# microSD.net
KiCad netlist of a schematic drawn in Altium Designer
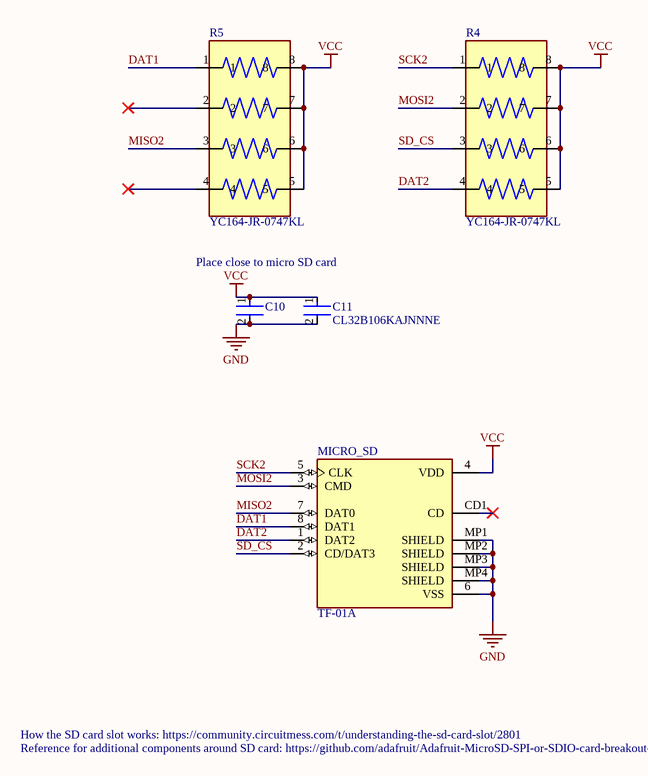
[diagram p0: microSD.SchDoc]

(export (version "E")
  (design (tool "Eeschema 10.0.6"))
  (components
    (comp (ref "C10")
      (value "CC0603KRX7R9BB104")
      (footprint "FP-CC0603-DA-MFG")
      (description "CAP CER 0.1UF 50V X7R 0603")
      (fields (field (name "MANUFACTURER") "YAGEO") (field (name "VOLTAGE") "50 V"))
      (libsource (lib "Altium Content Vault") (part "11868f565c42a9108669ba33697ecf6"))
    )
    (comp (ref "C11")
      (value "CL32B106KAJNNNE")
      (footprint "FP-CL32-IPC_B")
      (description "Cap Ceramic 10uF 25V X7R ±10% SMD 1210 +125°C Embossed T/R")
      (fields (field (name "TOLERANCE") "10%") (field (name "VOLTAGE") "25V"))
      (libsource (lib "Altium Content Vault") (part "b4654b650e69147ec39a6b967a45e02"))
    )
    (comp (ref "MICRO_SD")
      (value "TF-01A")
      (footprint "TF-01A")
      (description "Standard Card Edge Connectors")
      (fields (field (name "MF") "HRO Electronics Co., Ltd.") (field (name "LCSC PART #") "C91145"))
      (libsource (lib "TF-01A") (part "TF-01A"))
    )
    (comp (ref "R4")
      (value "YC164-JR-0747KL")
      (footprint "RESCAXE80P320X160X70-8N")
      (fields (field (name "MF") "Yageo") (field (name "LCSC PART #") "C779384"))
      (libsource (lib "YC164-JR-0747KL") (part "YC164-JR-0747KL"))
    )
    (comp (ref "R5")
      (value "YC164-JR-0747KL")
      (footprint "RESCAXE80P320X160X70-8N")
      (fields (field (name "MF") "Yageo") (field (name "LCSC PART #") "C779384"))
      (libsource (lib "YC164-JR-0747KL") (part "YC164-JR-0747KL"))
    )
  )
  (nets
    (net (code "1") (name "/DAT1") (class "Default")
      (node (ref "MICRO_SD") (pin "8") (pinfunction "DAT1_8") (pintype "bidirectional"))
      (node (ref "R5") (pin "1") (pinfunction "1_1") (pintype "passive"))
    )
    (net (code "2") (name "/DAT2") (class "Default")
      (node (ref "MICRO_SD") (pin "1") (pinfunction "DAT2_1") (pintype "bidirectional"))
      (node (ref "R4") (pin "4") (pinfunction "4_4") (pintype "passive"))
    )
    (net (code "3") (name "/MISO2") (class "Default")
      (node (ref "MICRO_SD") (pin "7") (pinfunction "DAT0_7") (pintype "bidirectional"))
      (node (ref "R5") (pin "3") (pinfunction "3_3") (pintype "passive"))
    )
    (net (code "4") (name "/MOSI2") (class "Default")
      (node (ref "MICRO_SD") (pin "3") (pinfunction "CMD_3") (pintype "bidirectional"))
      (node (ref "R4") (pin "2") (pinfunction "2_2") (pintype "passive"))
    )
    (net (code "5") (name "/SCK2") (class "Default")
      (node (ref "MICRO_SD") (pin "5") (pinfunction "CLK_5") (pintype "bidirectional"))
      (node (ref "R4") (pin "1") (pinfunction "1_1") (pintype "passive"))
    )
    (net (code "6") (name "/SD_CS") (class "Default")
      (node (ref "MICRO_SD") (pin "2") (pinfunction "CD/DAT3_2") (pintype "bidirectional"))
      (node (ref "R4") (pin "3") (pinfunction "3_3") (pintype "passive"))
    )
    (net (code "7") (name "GND") (class "Default")
      (node (ref "C10") (pin "2") (pinfunction "2_2") (pintype "passive"))
      (node (ref "C11") (pin "2") (pinfunction "2_2") (pintype "passive"))
      (node (ref "MICRO_SD") (pin "6") (pinfunction "VSS_6") (pintype "power_in"))
      (node (ref "MICRO_SD") (pin "MP1") (pinfunction "SHIELD_MP1") (pintype "power_in"))
      (node (ref "MICRO_SD") (pin "MP2") (pinfunction "SHIELD_MP2") (pintype "power_in"))
      (node (ref "MICRO_SD") (pin "MP3") (pinfunction "SHIELD_MP3") (pintype "power_in"))
      (node (ref "MICRO_SD") (pin "MP4") (pinfunction "SHIELD_MP4") (pintype "power_in"))
    )
    (net (code "8") (name "VCC") (class "Default")
      (node (ref "C10") (pin "1") (pinfunction "1_1") (pintype "passive"))
      (node (ref "C11") (pin "1") (pinfunction "1_1") (pintype "passive"))
      (node (ref "MICRO_SD") (pin "4") (pinfunction "VDD_4") (pintype "power_in"))
      (node (ref "R4") (pin "5") (pinfunction "5_5") (pintype "passive"))
      (node (ref "R4") (pin "6") (pinfunction "6_6") (pintype "passive"))
      (node (ref "R4") (pin "7") (pinfunction "7_7") (pintype "passive"))
      (node (ref "R4") (pin "8") (pinfunction "8_8") (pintype "passive"))
      (node (ref "R5") (pin "5") (pinfunction "5_5") (pintype "passive"))
      (node (ref "R5") (pin "6") (pinfunction "6_6") (pintype "passive"))
      (node (ref "R5") (pin "7") (pinfunction "7_7") (pintype "passive"))
      (node (ref "R5") (pin "8") (pinfunction "8_8") (pintype "passive"))
    )
    (net (code "9") (name "unconnected-(MICRO_SD-CD-PadCD1)") (class "Default")
      (node (ref "MICRO_SD") (pin "CD1") (pinfunction "CD_CD1") (pintype "passive+no_connect"))
    )
    (net (code "10") (name "unconnected-(R5-Pad2)") (class "Default")
      (node (ref "R5") (pin "2") (pinfunction "2_2") (pintype "passive+no_connect"))
    )
    (net (code "11") (name "unconnected-(R5-Pad4)") (class "Default")
      (node (ref "R5") (pin "4") (pinfunction "4_4") (pintype "passive+no_connect"))
    )
  )
)
